# V4.net
KiCad netlist of a schematic drawn in Altium Designer
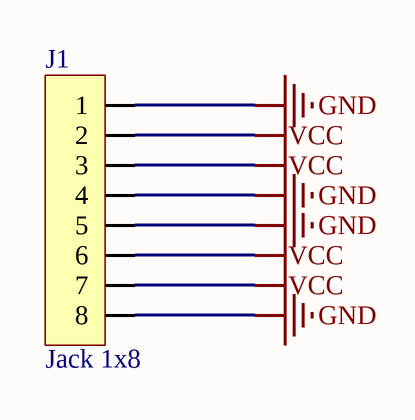
[diagram p0: 海关全向控制器电池接口板V4.SchDoc]

(export (version "E")
  (design (tool "Eeschema 10.0.6"))
  (components
    (comp (ref "J1")
      (value "Jack 1x8")
      (footprint "Pow-8P-F")
      (description "插座")
      (libsource (lib "Connector") (part "Jack 1x8"))
    )
  )
  (nets
    (net (code "1") (name "GND") (class "Default")
      (node (ref "J1") (pin "1") (pinfunction "1_1") (pintype "passive"))
      (node (ref "J1") (pin "4") (pinfunction "4_4") (pintype "passive"))
      (node (ref "J1") (pin "5") (pinfunction "5_5") (pintype "passive"))
      (node (ref "J1") (pin "8") (pinfunction "8_8") (pintype "passive"))
    )
    (net (code "2") (name "VCC") (class "Default")
      (node (ref "J1") (pin "2") (pinfunction "2_2") (pintype "passive"))
      (node (ref "J1") (pin "3") (pinfunction "3_3") (pintype "passive"))
      (node (ref "J1") (pin "6") (pinfunction "6_6") (pintype "passive"))
      (node (ref "J1") (pin "7") (pinfunction "7_7") (pintype "passive"))
    )
  )
)
